# countdown_timer.net
KiCad netlist of a schematic drawn in EAGLE
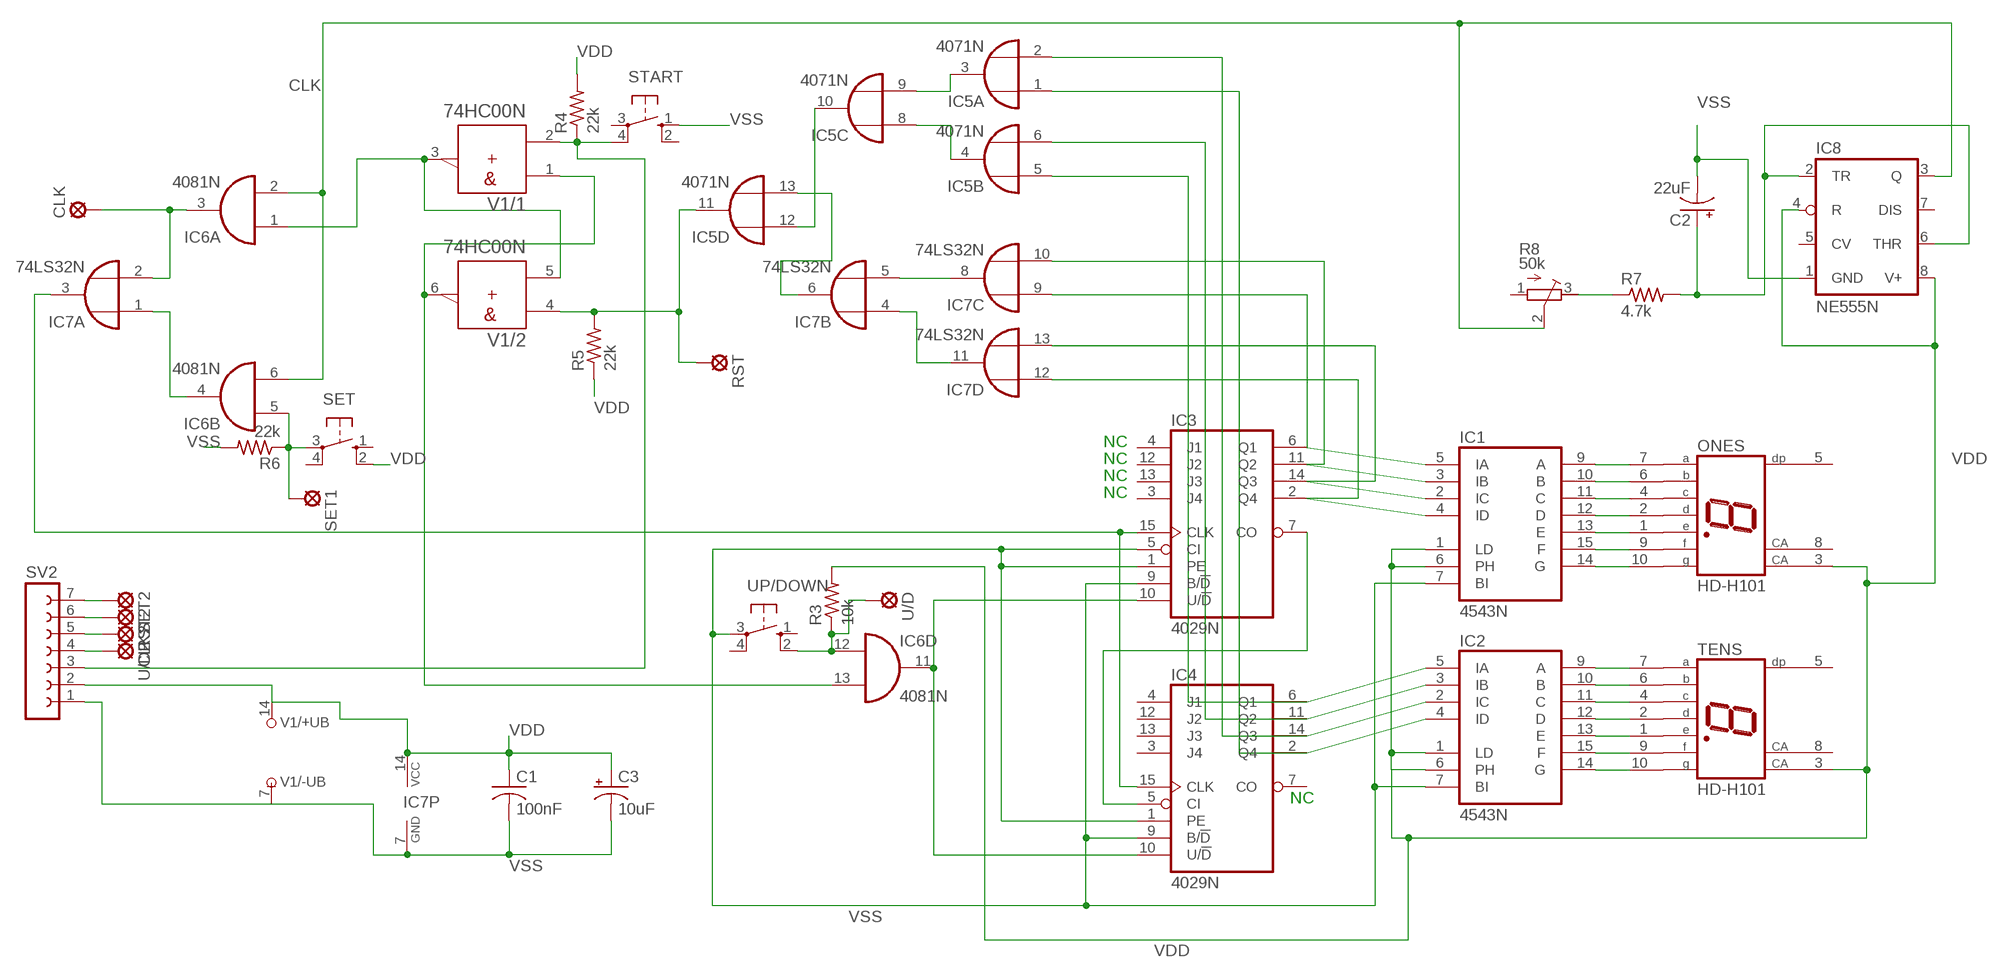
[diagram p0: schematic, sheet 1]

(export (version "E")
  (design (tool "Eeschema 10.0.6"))
  (components
    (comp (ref "C1")
      (value "100nF")
      (footprint "eagle-import:C025-024X044")
      (libsource (lib "eagle-import") (part "C-US025-024X044"))
    )
    (comp (ref "C2")
      (value "22uF")
      (footprint "eagle-import:E3,5-8")
      (libsource (lib "eagle-import") (part "CPOL-USE3.5-8"))
    )
    (comp (ref "C3")
      (value "10uF")
      (footprint "eagle-import:E3,5-8")
      (libsource (lib "eagle-import") (part "CPOL-USE3.5-8"))
    )
    (comp (ref "CLK")
      (value "LSP10")
      (footprint "eagle-import:LSP10")
      (libsource (lib "eagle-import") (part "LSP10"))
    )
    (comp (ref "CLK2")
      (value "LSP10")
      (footprint "eagle-import:LSP10")
      (libsource (lib "eagle-import") (part "LSP10"))
    )
    (comp (ref "IC1")
      (value "4543N")
      (footprint "eagle-import:DIL16")
      (libsource (lib "eagle-import") (part "4543N"))
    )
    (comp (ref "IC2")
      (value "4543N")
      (footprint "eagle-import:DIL16")
      (libsource (lib "eagle-import") (part "4543N"))
    )
    (comp (ref "IC3")
      (value "4029N")
      (footprint "eagle-import:DIL16")
      (libsource (lib "eagle-import") (part "4029N"))
    )
    (comp (ref "IC4")
      (value "4029N")
      (footprint "eagle-import:DIL16")
      (libsource (lib "eagle-import") (part "4029N"))
    )
    (comp (ref "IC5")
      (value "4071N")
      (footprint "eagle-import:DIL14")
      (libsource (lib "eagle-import") (part "4071N"))
    )
    (comp (ref "IC6")
      (value "4081N")
      (footprint "eagle-import:DIL14")
      (libsource (lib "eagle-import") (part "4081N"))
    )
    (comp (ref "IC7")
      (value "74LS32N")
      (footprint "eagle-import:DIL14")
      (libsource (lib "eagle-import") (part "7432NLS"))
    )
    (comp (ref "IC8")
      (value "NE555N")
      (footprint "eagle-import:DIL08")
      (libsource (lib "eagle-import") (part "555NNE"))
    )
    (comp (ref "ONES")
      (value "HD-H101")
      (footprint "eagle-import:HDSP-M")
      (libsource (lib "eagle-import") (part "HD-H101"))
    )
    (comp (ref "R3")
      (value "10k")
      (footprint "eagle-import:0204_5")
      (libsource (lib "eagle-import") (part "R-US_0204/5"))
    )
    (comp (ref "R4")
      (value "22k")
      (footprint "eagle-import:0204_5")
      (libsource (lib "eagle-import") (part "R-US_0204/5"))
    )
    (comp (ref "R5")
      (value "22k")
      (footprint "eagle-import:0204_5")
      (libsource (lib "eagle-import") (part "R-US_0204/5"))
    )
    (comp (ref "R6")
      (value "22k")
      (footprint "eagle-import:0204_5")
      (libsource (lib "eagle-import") (part "R-US_0204/5"))
    )
    (comp (ref "R7")
      (value "4.7k")
      (footprint "eagle-import:0204_5")
      (libsource (lib "eagle-import") (part "R-US_0204/5"))
    )
    (comp (ref "R8")
      (value "50k")
      (footprint "eagle-import:RTRIM3339P")
      (libsource (lib "eagle-import") (part "R-TRIMM3339P"))
    )
    (comp (ref "RST")
      (value "LSP10")
      (footprint "eagle-import:LSP10")
      (libsource (lib "eagle-import") (part "LSP10"))
    )
    (comp (ref "RST2")
      (value "LSP10")
      (footprint "eagle-import:LSP10")
      (libsource (lib "eagle-import") (part "LSP10"))
    )
    (comp (ref "SET")
      (value "10-XX")
      (footprint "eagle-import:B3F-10XX")
      (fields (field (name "MPN") "B3F-1000"))
      (libsource (lib "eagle-import") (part "10-XX"))
    )
    (comp (ref "SET1")
      (value "LSP10")
      (footprint "eagle-import:LSP10")
      (libsource (lib "eagle-import") (part "LSP10"))
    )
    (comp (ref "SET2")
      (value "LSP10")
      (footprint "eagle-import:LSP10")
      (libsource (lib "eagle-import") (part "LSP10"))
    )
    (comp (ref "START")
      (value "10-XX")
      (footprint "eagle-import:B3F-10XX")
      (fields (field (name "MPN") "B3F-1000"))
      (libsource (lib "eagle-import") (part "10-XX"))
    )
    (comp (ref "SV2")
      (value "FE07-1")
      (footprint "eagle-import:FE07")
      (libsource (lib "eagle-import") (part "FE07-1"))
    )
    (comp (ref "TENS")
      (value "HD-H101")
      (footprint "eagle-import:HDSP-M")
      (libsource (lib "eagle-import") (part "HD-H101"))
    )
    (comp (ref "U/D")
      (value "LSP10")
      (footprint "eagle-import:LSP10")
      (libsource (lib "eagle-import") (part "LSP10"))
    )
    (comp (ref "U/D2")
      (value "LSP10")
      (footprint "eagle-import:LSP10")
      (libsource (lib "eagle-import") (part "LSP10"))
    )
    (comp (ref "UP/DOWN")
      (value "10-XX")
      (footprint "eagle-import:B3F-10XX")
      (fields (field (name "MPN") "B3F-1000"))
      (libsource (lib "eagle-import") (part "10-XX"))
    )
    (comp (ref "V1")
      (value "74HC00N")
      (footprint "eagle-import:DIL14")
      (libsource (lib "eagle-import") (part "7400NHC"))
    )
  )
  (nets
    (net (code "1") (name "/CLK") (class "Default")
      (node (ref "IC6") (pin "2") (pinfunction "I1_2") (pintype "input"))
      (node (ref "IC6") (pin "6") (pinfunction "I1_6") (pintype "input"))
      (node (ref "IC8") (pin "3") (pinfunction "Q_3") (pintype "output"))
      (node (ref "R8") (pin "2") (pinfunction "S_2") (pintype "passive"))
    )
    (net (code "2") (name "/VDD") (class "Default")
      (node (ref "C1") (pin "1") (pinfunction "1_1") (pintype "passive"))
      (node (ref "C3") (pin "+") (pinfunction "+_+") (pintype "passive"))
      (node (ref "IC1") (pin "1") (pinfunction "LD_1") (pintype "input"))
      (node (ref "IC1") (pin "6") (pinfunction "PH_6") (pintype "input"))
      (node (ref "IC2") (pin "1") (pinfunction "LD_1") (pintype "input"))
      (node (ref "IC2") (pin "6") (pinfunction "PH_6") (pintype "input"))
      (node (ref "IC7") (pin "14") (pinfunction "VCC_14") (pintype "power_in"))
      (node (ref "IC8") (pin "4") (pinfunction "R_4") (pintype "input"))
      (node (ref "IC8") (pin "8") (pinfunction "V+_8") (pintype "power_in"))
      (node (ref "ONES") (pin "3") (pinfunction "CA_3") (pintype "passive"))
      (node (ref "R3") (pin "2") (pinfunction "2_2") (pintype "passive"))
      (node (ref "R4") (pin "2") (pinfunction "2_2") (pintype "passive"))
      (node (ref "R5") (pin "1") (pinfunction "1_1") (pintype "passive"))
      (node (ref "SET") (pin "2") (pinfunction "S1_2") (pintype "passive"))
      (node (ref "SV2") (pin "2") (pinfunction "2_2") (pintype "passive"))
      (node (ref "TENS") (pin "3") (pinfunction "CA_3") (pintype "passive"))
      (node (ref "V1") (pin "14") (pinfunction "+UB_14") (pintype "power_in"))
    )
    (net (code "3") (name "/VSS") (class "Default")
      (node (ref "C1") (pin "2") (pinfunction "2_2") (pintype "passive"))
      (node (ref "C2") (pin "-") (pinfunction "-_-") (pintype "passive"))
      (node (ref "C3") (pin "-") (pinfunction "-_-") (pintype "passive"))
      (node (ref "IC1") (pin "7") (pinfunction "BI_7") (pintype "input"))
      (node (ref "IC2") (pin "7") (pinfunction "BI_7") (pintype "input"))
      (node (ref "IC3") (pin "1") (pinfunction "PE_1") (pintype "input"))
      (node (ref "IC3") (pin "5") (pinfunction "CI_5") (pintype "input"))
      (node (ref "IC3") (pin "9") (pinfunction "B/~{D}_9") (pintype "input"))
      (node (ref "IC4") (pin "1") (pinfunction "PE_1") (pintype "input"))
      (node (ref "IC4") (pin "9") (pinfunction "B/~{D}_9") (pintype "input"))
      (node (ref "IC7") (pin "7") (pinfunction "GND_7") (pintype "power_in"))
      (node (ref "IC8") (pin "1") (pinfunction "GND_1") (pintype "power_in"))
      (node (ref "R6") (pin "2") (pinfunction "2_2") (pintype "passive"))
      (node (ref "START") (pin "1") (pinfunction "S_1") (pintype "passive"))
      (node (ref "SV2") (pin "1") (pinfunction "1_1") (pintype "passive"))
      (node (ref "UP/DOWN") (pin "3") (pinfunction "P_3") (pintype "passive"))
      (node (ref "V1") (pin "7") (pinfunction "-UB_7") (pintype "power_in"))
    )
    (net (code "4") (name "Net-(CLK2-PadMP)") (class "Default")
      (node (ref "CLK2") (pin "MP") (pinfunction "MP_MP") (pintype "passive"))
      (node (ref "SV2") (pin "5") (pinfunction "5_5") (pintype "passive"))
    )
    (net (code "5") (name "Net-(IC1A-A)") (class "Default")
      (node (ref "IC1") (pin "9") (pinfunction "A_9") (pintype "output"))
      (node (ref "ONES") (pin "7") (pinfunction "A_7") (pintype "passive"))
    )
    (net (code "6") (name "Net-(IC1A-B)") (class "Default")
      (node (ref "IC1") (pin "10") (pinfunction "B_10") (pintype "output"))
      (node (ref "ONES") (pin "6") (pinfunction "B_6") (pintype "passive"))
    )
    (net (code "7") (name "Net-(IC1A-C)") (class "Default")
      (node (ref "IC1") (pin "11") (pinfunction "C_11") (pintype "output"))
      (node (ref "ONES") (pin "4") (pinfunction "C_4") (pintype "passive"))
    )
    (net (code "8") (name "Net-(IC1A-D)") (class "Default")
      (node (ref "IC1") (pin "12") (pinfunction "D_12") (pintype "output"))
      (node (ref "ONES") (pin "2") (pinfunction "D_2") (pintype "passive"))
    )
    (net (code "9") (name "Net-(IC1A-E)") (class "Default")
      (node (ref "IC1") (pin "13") (pinfunction "E_13") (pintype "output"))
      (node (ref "ONES") (pin "1") (pinfunction "E_1") (pintype "passive"))
    )
    (net (code "10") (name "Net-(IC1A-F)") (class "Default")
      (node (ref "IC1") (pin "15") (pinfunction "F_15") (pintype "output"))
      (node (ref "ONES") (pin "9") (pinfunction "F_9") (pintype "passive"))
    )
    (net (code "11") (name "Net-(IC1A-G)") (class "Default")
      (node (ref "IC1") (pin "14") (pinfunction "G_14") (pintype "output"))
      (node (ref "ONES") (pin "10") (pinfunction "G_10") (pintype "passive"))
    )
    (net (code "12") (name "Net-(IC1A-IA)") (class "Default")
      (node (ref "IC1") (pin "5") (pinfunction "IA_5") (pintype "input"))
      (node (ref "IC3") (pin "6") (pinfunction "Q1_6") (pintype "output"))
      (node (ref "IC7") (pin "9") (pinfunction "I0_9") (pintype "input"))
    )
    (net (code "13") (name "Net-(IC1A-IB)") (class "Default")
      (node (ref "IC1") (pin "3") (pinfunction "IB_3") (pintype "input"))
      (node (ref "IC3") (pin "11") (pinfunction "Q2_11") (pintype "output"))
      (node (ref "IC7") (pin "10") (pinfunction "I1_10") (pintype "input"))
    )
    (net (code "14") (name "Net-(IC1A-IC)") (class "Default")
      (node (ref "IC1") (pin "2") (pinfunction "IC_2") (pintype "input"))
      (node (ref "IC3") (pin "14") (pinfunction "Q3_14") (pintype "output"))
      (node (ref "IC7") (pin "13") (pinfunction "I1_13") (pintype "input"))
    )
    (net (code "15") (name "Net-(IC1A-ID)") (class "Default")
      (node (ref "IC1") (pin "4") (pinfunction "ID_4") (pintype "input"))
      (node (ref "IC3") (pin "2") (pinfunction "Q4_2") (pintype "output"))
      (node (ref "IC7") (pin "12") (pinfunction "I0_12") (pintype "input"))
    )
    (net (code "16") (name "Net-(IC2A-A)") (class "Default")
      (node (ref "IC2") (pin "9") (pinfunction "A_9") (pintype "output"))
      (node (ref "TENS") (pin "7") (pinfunction "A_7") (pintype "passive"))
    )
    (net (code "17") (name "Net-(IC2A-B)") (class "Default")
      (node (ref "IC2") (pin "10") (pinfunction "B_10") (pintype "output"))
      (node (ref "TENS") (pin "6") (pinfunction "B_6") (pintype "passive"))
    )
    (net (code "18") (name "Net-(IC2A-C)") (class "Default")
      (node (ref "IC2") (pin "11") (pinfunction "C_11") (pintype "output"))
      (node (ref "TENS") (pin "4") (pinfunction "C_4") (pintype "passive"))
    )
    (net (code "19") (name "Net-(IC2A-D)") (class "Default")
      (node (ref "IC2") (pin "12") (pinfunction "D_12") (pintype "output"))
      (node (ref "TENS") (pin "2") (pinfunction "D_2") (pintype "passive"))
    )
    (net (code "20") (name "Net-(IC2A-E)") (class "Default")
      (node (ref "IC2") (pin "13") (pinfunction "E_13") (pintype "output"))
      (node (ref "TENS") (pin "1") (pinfunction "E_1") (pintype "passive"))
    )
    (net (code "21") (name "Net-(IC2A-F)") (class "Default")
      (node (ref "IC2") (pin "15") (pinfunction "F_15") (pintype "output"))
      (node (ref "TENS") (pin "9") (pinfunction "F_9") (pintype "passive"))
    )
    (net (code "22") (name "Net-(IC2A-G)") (class "Default")
      (node (ref "IC2") (pin "14") (pinfunction "G_14") (pintype "output"))
      (node (ref "TENS") (pin "10") (pinfunction "G_10") (pintype "passive"))
    )
    (net (code "23") (name "Net-(IC2A-IA)") (class "Default")
      (node (ref "IC2") (pin "5") (pinfunction "IA_5") (pintype "input"))
      (node (ref "IC4") (pin "6") (pinfunction "Q1_6") (pintype "output"))
      (node (ref "IC5") (pin "5") (pinfunction "I0_5") (pintype "input"))
    )
    (net (code "24") (name "Net-(IC2A-IB)") (class "Default")
      (node (ref "IC2") (pin "3") (pinfunction "IB_3") (pintype "input"))
      (node (ref "IC4") (pin "11") (pinfunction "Q2_11") (pintype "output"))
      (node (ref "IC5") (pin "6") (pinfunction "I1_6") (pintype "input"))
    )
    (net (code "25") (name "Net-(IC2A-IC)") (class "Default")
      (node (ref "IC2") (pin "2") (pinfunction "IC_2") (pintype "input"))
      (node (ref "IC4") (pin "14") (pinfunction "Q3_14") (pintype "output"))
      (node (ref "IC5") (pin "2") (pinfunction "I1_2") (pintype "input"))
    )
    (net (code "26") (name "Net-(IC2A-ID)") (class "Default")
      (node (ref "IC2") (pin "4") (pinfunction "ID_4") (pintype "input"))
      (node (ref "IC4") (pin "2") (pinfunction "Q4_2") (pintype "output"))
      (node (ref "IC5") (pin "1") (pinfunction "I0_1") (pintype "input"))
    )
    (net (code "27") (name "Net-(IC3A-CLK)") (class "Default")
      (node (ref "IC3") (pin "15") (pinfunction "CLK_15") (pintype "input"))
      (node (ref "IC4") (pin "15") (pinfunction "CLK_15") (pintype "input"))
      (node (ref "IC7") (pin "3") (pinfunction "O_3") (pintype "output"))
    )
    (net (code "28") (name "Net-(IC3A-CO)") (class "Default")
      (node (ref "IC3") (pin "7") (pinfunction "CO_7") (pintype "output"))
      (node (ref "IC4") (pin "5") (pinfunction "CI_5") (pintype "input"))
    )
    (net (code "29") (name "Net-(IC3A-U{slash}~{D})") (class "Default")
      (node (ref "IC3") (pin "10") (pinfunction "U/~{D}_10") (pintype "input"))
      (node (ref "IC4") (pin "10") (pinfunction "U/~{D}_10") (pintype "input"))
      (node (ref "IC6") (pin "11") (pinfunction "O_11") (pintype "output"))
    )
    (net (code "30") (name "Net-(IC5A-O)") (class "Default")
      (node (ref "IC5") (pin "3") (pinfunction "O_3") (pintype "output"))
      (node (ref "IC5") (pin "9") (pinfunction "I1_9") (pintype "input"))
    )
    (net (code "31") (name "Net-(IC5B-O)") (class "Default")
      (node (ref "IC5") (pin "4") (pinfunction "O_4") (pintype "output"))
      (node (ref "IC5") (pin "8") (pinfunction "I0_8") (pintype "input"))
    )
    (net (code "32") (name "Net-(IC5C-O)") (class "Default")
      (node (ref "IC5") (pin "10") (pinfunction "O_10") (pintype "output"))
      (node (ref "IC5") (pin "12") (pinfunction "I0_12") (pintype "input"))
    )
    (net (code "33") (name "Net-(IC5D-I1)") (class "Default")
      (node (ref "IC5") (pin "13") (pinfunction "I1_13") (pintype "input"))
      (node (ref "IC7") (pin "6") (pinfunction "O_6") (pintype "output"))
    )
    (net (code "34") (name "Net-(IC5D-O)") (class "Default")
      (node (ref "IC5") (pin "11") (pinfunction "O_11") (pintype "output"))
      (node (ref "R5") (pin "2") (pinfunction "2_2") (pintype "passive"))
      (node (ref "RST") (pin "MP") (pinfunction "MP_MP") (pintype "passive"))
      (node (ref "V1") (pin "4") (pinfunction "A_4") (pintype "input"))
    )
    (net (code "35") (name "Net-(IC6A-I0)") (class "Default")
      (node (ref "IC6") (pin "1") (pinfunction "I0_1") (pintype "input"))
      (node (ref "V1") (pin "3") (pinfunction "Y_3") (pintype "output"))
      (node (ref "V1") (pin "5") (pinfunction "B_5") (pintype "input"))
    )
    (net (code "36") (name "Net-(IC6A-O)") (class "Default")
      (node (ref "CLK") (pin "MP") (pinfunction "MP_MP") (pintype "passive"))
      (node (ref "IC6") (pin "3") (pinfunction "O_3") (pintype "output"))
      (node (ref "IC7") (pin "2") (pinfunction "I1_2") (pintype "input"))
    )
    (net (code "37") (name "Net-(IC6B-I0)") (class "Default")
      (node (ref "IC6") (pin "5") (pinfunction "I0_5") (pintype "input"))
      (node (ref "R6") (pin "1") (pinfunction "1_1") (pintype "passive"))
      (node (ref "SET") (pin "3") (pinfunction "P_3") (pintype "passive"))
      (node (ref "SET1") (pin "MP") (pinfunction "MP_MP") (pintype "passive"))
    )
    (net (code "38") (name "Net-(IC6B-O)") (class "Default")
      (node (ref "IC6") (pin "4") (pinfunction "O_4") (pintype "output"))
      (node (ref "IC7") (pin "1") (pinfunction "I0_1") (pintype "input"))
    )
    (net (code "39") (name "Net-(IC6D-I0)") (class "Default")
      (node (ref "IC6") (pin "12") (pinfunction "I0_12") (pintype "input"))
      (node (ref "R3") (pin "1") (pinfunction "1_1") (pintype "passive"))
      (node (ref "U/D") (pin "MP") (pinfunction "MP_MP") (pintype "passive"))
      (node (ref "UP/DOWN") (pin "2") (pinfunction "S1_2") (pintype "passive"))
    )
    (net (code "40") (name "Net-(IC6D-I1)") (class "Default")
      (node (ref "IC6") (pin "13") (pinfunction "I1_13") (pintype "input"))
      (node (ref "V1") (pin "1") (pinfunction "A_1") (pintype "input"))
      (node (ref "V1") (pin "6") (pinfunction "Y_6") (pintype "output"))
    )
    (net (code "41") (name "Net-(IC7B-I0)") (class "Default")
      (node (ref "IC7") (pin "11") (pinfunction "O_11") (pintype "output"))
      (node (ref "IC7") (pin "4") (pinfunction "I0_4") (pintype "input"))
    )
    (net (code "42") (name "Net-(IC7B-I1)") (class "Default")
      (node (ref "IC7") (pin "5") (pinfunction "I1_5") (pintype "input"))
      (node (ref "IC7") (pin "8") (pinfunction "O_8") (pintype "output"))
    )
    (net (code "43") (name "Net-(IC8-THR)") (class "Default")
      (node (ref "C2") (pin "+") (pinfunction "+_+") (pintype "passive"))
      (node (ref "IC8") (pin "2") (pinfunction "TR_2") (pintype "input"))
      (node (ref "IC8") (pin "6") (pinfunction "THR_6") (pintype "input"))
      (node (ref "R7") (pin "2") (pinfunction "2_2") (pintype "passive"))
    )
    (net (code "44") (name "Net-(R8-E)") (class "Default")
      (node (ref "R7") (pin "1") (pinfunction "1_1") (pintype "passive"))
      (node (ref "R8") (pin "3") (pinfunction "E_3") (pintype "passive"))
    )
    (net (code "45") (name "Net-(RST2-PadMP)") (class "Default")
      (node (ref "RST2") (pin "MP") (pinfunction "MP_MP") (pintype "passive"))
      (node (ref "SV2") (pin "6") (pinfunction "6_6") (pintype "passive"))
    )
    (net (code "46") (name "Net-(SET2-PadMP)") (class "Default")
      (node (ref "SET2") (pin "MP") (pinfunction "MP_MP") (pintype "passive"))
      (node (ref "SV2") (pin "7") (pinfunction "7_7") (pintype "passive"))
    )
    (net (code "47") (name "Net-(START-P1)") (class "Default")
      (node (ref "R4") (pin "1") (pinfunction "1_1") (pintype "passive"))
      (node (ref "START") (pin "4") (pinfunction "P1_4") (pintype "passive"))
      (node (ref "SV2") (pin "3") (pinfunction "3_3") (pintype "passive"))
      (node (ref "V1") (pin "2") (pinfunction "B_2") (pintype "input"))
    )
    (net (code "48") (name "Net-(SV2-Pad4)") (class "Default")
      (node (ref "SV2") (pin "4") (pinfunction "4_4") (pintype "passive"))
      (node (ref "U/D2") (pin "MP") (pinfunction "MP_MP") (pintype "passive"))
    )
    (net (code "49") (name "unconnected-(IC3A-J1-Pad4)") (class "Default")
      (node (ref "IC3") (pin "4") (pinfunction "J1_4") (pintype "input"))
    )
    (net (code "50") (name "unconnected-(IC3A-J2-Pad12)") (class "Default")
      (node (ref "IC3") (pin "12") (pinfunction "J2_12") (pintype "input"))
    )
    (net (code "51") (name "unconnected-(IC3A-J3-Pad13)") (class "Default")
      (node (ref "IC3") (pin "13") (pinfunction "J3_13") (pintype "input"))
    )
    (net (code "52") (name "unconnected-(IC3A-J4-Pad3)") (class "Default")
      (node (ref "IC3") (pin "3") (pinfunction "J4_3") (pintype "input"))
    )
    (net (code "53") (name "unconnected-(IC4A-CO-Pad7)") (class "Default")
      (node (ref "IC4") (pin "7") (pinfunction "CO_7") (pintype "output"))
    )
    (net (code "54") (name "unconnected-(IC4A-J1-Pad4)") (class "Default")
      (node (ref "IC4") (pin "4") (pinfunction "J1_4") (pintype "input"))
    )
    (net (code "55") (name "unconnected-(IC4A-J2-Pad12)") (class "Default")
      (node (ref "IC4") (pin "12") (pinfunction "J2_12") (pintype "input"))
    )
    (net (code "56") (name "unconnected-(IC4A-J3-Pad13)") (class "Default")
      (node (ref "IC4") (pin "13") (pinfunction "J3_13") (pintype "input"))
    )
    (net (code "57") (name "unconnected-(IC4A-J4-Pad3)") (class "Default")
      (node (ref "IC4") (pin "3") (pinfunction "J4_3") (pintype "input"))
    )
    (net (code "58") (name "unconnected-(IC8-CV-Pad5)") (class "Default")
      (node (ref "IC8") (pin "5") (pinfunction "CV_5") (pintype "input"))
    )
    (net (code "59") (name "unconnected-(IC8-DIS-Pad7)") (class "Default")
      (node (ref "IC8") (pin "7") (pinfunction "DIS_7") (pintype "input"))
    )
    (net (code "60") (name "unconnected-(ONES-CA-Pad8)") (class "Default")
      (node (ref "ONES") (pin "8") (pinfunction "CA_8") (pintype "passive"))
    )
    (net (code "61") (name "unconnected-(ONES-DP-Pad5)") (class "Default")
      (node (ref "ONES") (pin "5") (pinfunction "DP_5") (pintype "passive"))
    )
    (net (code "62") (name "unconnected-(R8-A-Pad1)") (class "Default")
      (node (ref "R8") (pin "1") (pinfunction "A_1") (pintype "passive"))
    )
    (net (code "63") (name "unconnected-(SET-P1-Pad4)") (class "Default")
      (node (ref "SET") (pin "4") (pinfunction "P1_4") (pintype "passive"))
    )
    (net (code "64") (name "unconnected-(SET-S-Pad1)") (class "Default")
      (node (ref "SET") (pin "1") (pinfunction "S_1") (pintype "passive"))
    )
    (net (code "65") (name "unconnected-(START-P-Pad3)") (class "Default")
      (node (ref "START") (pin "3") (pinfunction "P_3") (pintype "passive"))
    )
    (net (code "66") (name "unconnected-(START-S1-Pad2)") (class "Default")
      (node (ref "START") (pin "2") (pinfunction "S1_2") (pintype "passive"))
    )
    (net (code "67") (name "unconnected-(TENS-CA-Pad8)") (class "Default")
      (node (ref "TENS") (pin "8") (pinfunction "CA_8") (pintype "passive"))
    )
    (net (code "68") (name "unconnected-(TENS-DP-Pad5)") (class "Default")
      (node (ref "TENS") (pin "5") (pinfunction "DP_5") (pintype "passive"))
    )
    (net (code "69") (name "unconnected-(UP/DOWN-P1-Pad4)") (class "Default")
      (node (ref "UP/DOWN") (pin "4") (pinfunction "P1_4") (pintype "passive"))
    )
    (net (code "70") (name "unconnected-(UP/DOWN-S-Pad1)") (class "Default")
      (node (ref "UP/DOWN") (pin "1") (pinfunction "S_1") (pintype "passive"))
    )
  )
)
